# Sheet3.net
KiCad netlist of a schematic drawn in Altium Designer
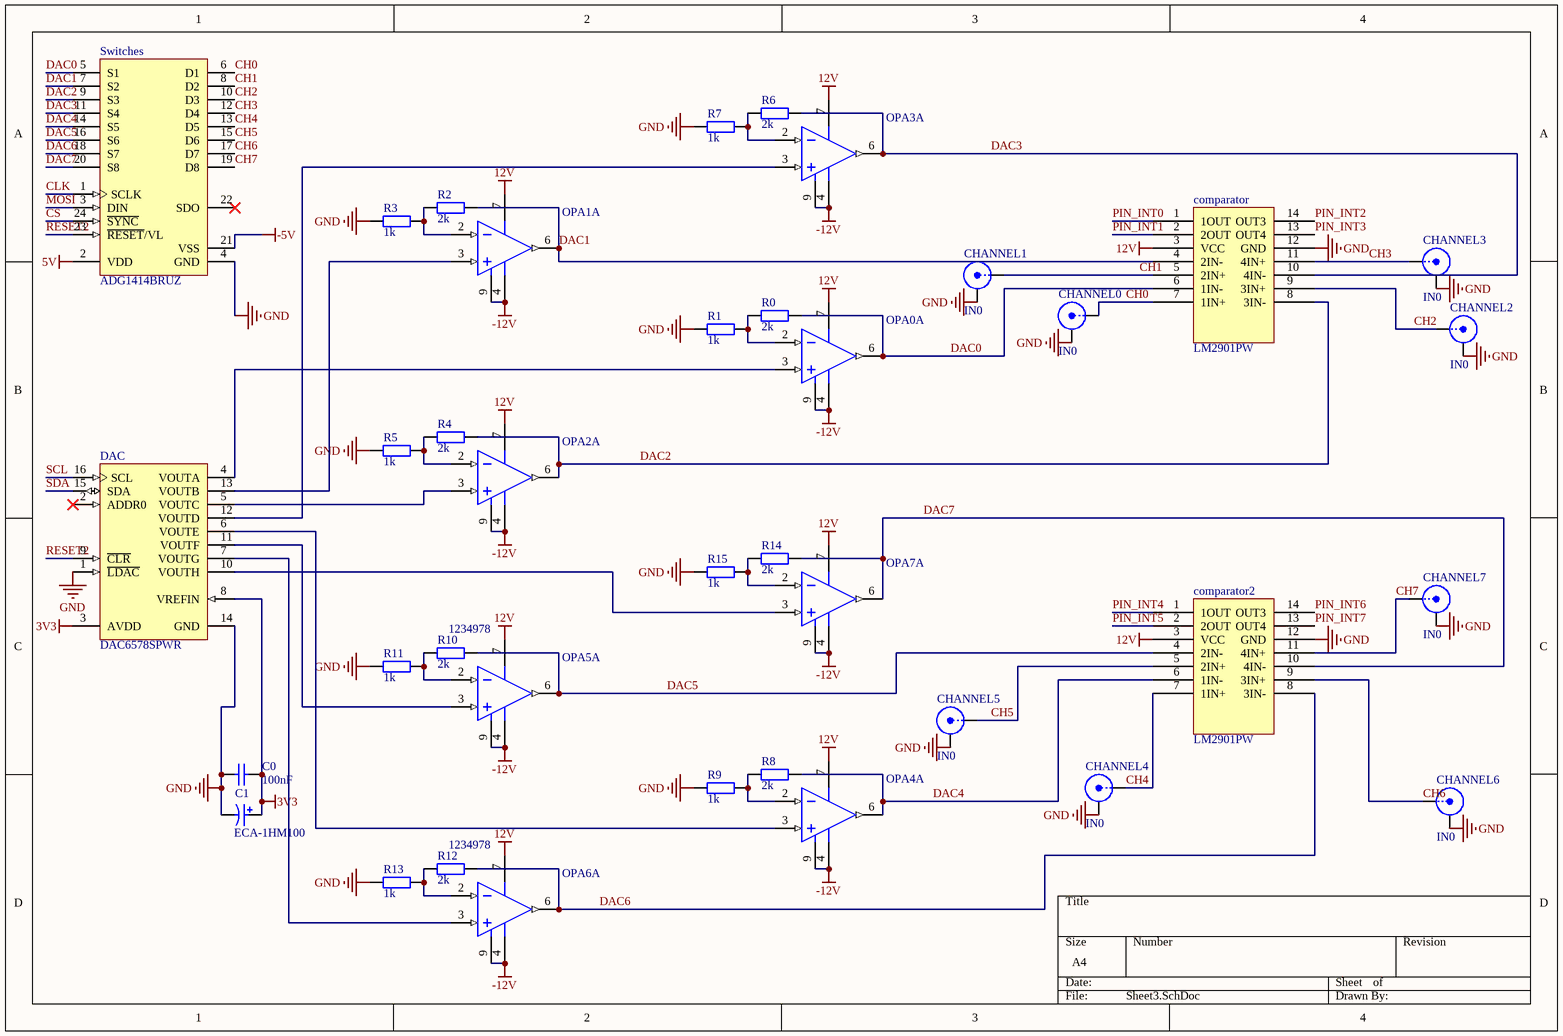
[diagram p0: Sheet3.SchDoc]

(export (version "E")
  (design (tool "Eeschema 10.0.6"))
  (components
    (comp (ref "C0")
      (value "100nF")
      (footprint "C0805")
      (description "Capacitor Cer 50V 0805 Vishay X7R")
      (libsource (lib "capacitors") (part "Ceramic 100nF/50V"))
    )
    (comp (ref "C1")
      (value "ECA-1HM100")
      (footprint "CAPPR55-200-1100X500X1200")
      (description "Aluminum Electrolytic Capacitor, 10 uF, +/- 20%, 50 V, -40 to 85 degC, 2-Pin THD, RoHS, Bulk")
      (libsource (lib "Altium Content Vault") (part "CMP-1665-00038-1"))
    )
    (comp (ref "CHANNEL0")
      (value "IN0")
      (footprint "connectors:SMB")
      (description "SMB Straight Connector")
      (fields (field (name "PUBLISHER") "Altium Limited"))
      (libsource (lib "connectors") (part "SMB"))
    )
    (comp (ref "CHANNEL1")
      (value "IN0")
      (footprint "connectors:SMB")
      (description "SMB Straight Connector")
      (fields (field (name "PUBLISHER") "Altium Limited"))
      (libsource (lib "connectors") (part "SMB"))
    )
    (comp (ref "CHANNEL2")
      (value "IN0")
      (footprint "connectors:SMB")
      (description "SMB Straight Connector")
      (fields (field (name "PUBLISHER") "Altium Limited"))
      (libsource (lib "connectors") (part "SMB"))
    )
    (comp (ref "CHANNEL3")
      (value "IN0")
      (footprint "connectors:SMB")
      (description "SMB Straight Connector")
      (fields (field (name "PUBLISHER") "Altium Limited"))
      (libsource (lib "connectors") (part "SMB"))
    )
    (comp (ref "CHANNEL4")
      (value "IN0")
      (footprint "connectors:SMB")
      (description "SMB Straight Connector")
      (fields (field (name "PUBLISHER") "Altium Limited"))
      (libsource (lib "connectors") (part "SMB"))
    )
    (comp (ref "CHANNEL5")
      (value "IN0")
      (footprint "connectors:SMB")
      (description "SMB Straight Connector")
      (fields (field (name "PUBLISHER") "Altium Limited"))
      (libsource (lib "connectors") (part "SMB"))
    )
    (comp (ref "CHANNEL6")
      (value "IN0")
      (footprint "connectors:SMB")
      (description "SMB Straight Connector")
      (fields (field (name "PUBLISHER") "Altium Limited"))
      (libsource (lib "connectors") (part "SMB"))
    )
    (comp (ref "CHANNEL7")
      (value "IN0")
      (footprint "connectors:SMB")
      (description "SMB Straight Connector")
      (fields (field (name "PUBLISHER") "Altium Limited"))
      (libsource (lib "connectors") (part "SMB"))
    )
    (comp (ref "comparator")
      (value "LM2901PW")
      (footprint "TSSOP-14")
      (libsource (lib "schlib") (part "LM2901PW"))
    )
    (comp (ref "comparator2")
      (value "LM2901PW")
      (footprint "TSSOP-14")
      (libsource (lib "schlib") (part "LM2901PW"))
    )
    (comp (ref "DAC")
      (value "DAC6578SPWR")
      (footprint "TI-PW16_N")
      (fields (field (name "MANUFACTURER") "Texas Instruments"))
      (libsource (lib "Altium Content Vault") (part "CMP-0004-01130-1"))
    )
    (comp (ref "OPA0")
      (value "THS3001IDGNG4")
      (footprint "TI-DGN8-1760X1425TP_N")
      (fields (field (name "MANUFACTURER") "Texas Instruments"))
      (libsource (lib "Altium Content Vault") (part "CMP-0016-00120-1"))
    )
    (comp (ref "OPA1")
      (value "THS3001IDGNG4")
      (footprint "TI-DGN8-1760X1425TP_N")
      (fields (field (name "MANUFACTURER") "Texas Instruments"))
      (libsource (lib "Altium Content Vault") (part "CMP-0016-00120-1"))
    )
    (comp (ref "OPA2")
      (value "THS3001IDGNG4")
      (footprint "TI-DGN8-1760X1425TP_N")
      (fields (field (name "MANUFACTURER") "Texas Instruments"))
      (libsource (lib "Altium Content Vault") (part "CMP-0016-00120-1"))
    )
    (comp (ref "OPA3")
      (value "THS3001IDGNG4")
      (footprint "TI-DGN8-1760X1425TP_N")
      (fields (field (name "MANUFACTURER") "Texas Instruments"))
      (libsource (lib "Altium Content Vault") (part "CMP-0016-00120-1"))
    )
    (comp (ref "OPA4")
      (value "THS3001IDGNG4")
      (footprint "TI-DGN8-1760X1425TP_N")
      (fields (field (name "MANUFACTURER") "Texas Instruments"))
      (libsource (lib "Altium Content Vault") (part "CMP-0016-00120-1"))
    )
    (comp (ref "OPA5")
      (value "THS3001IDGNG4")
      (footprint "TI-DGN8-1760X1425TP_N")
      (fields
        (field (name "MANUFACTURER") "Texas Instruments")
        (field (name "SUPPLIER PART NUMBER 1") "1234978")
      )
      (libsource (lib "Altium Content Vault") (part "CMP-0016-00120-1"))
    )
    (comp (ref "OPA6")
      (value "THS3001IDGNG4")
      (footprint "TI-DGN8-1760X1425TP_N")
      (fields
        (field (name "MANUFACTURER") "Texas Instruments")
        (field (name "SUPPLIER PART NUMBER 1") "1234978")
      )
      (libsource (lib "Altium Content Vault") (part "CMP-0016-00120-1"))
    )
    (comp (ref "OPA7")
      (value "THS3001IDGNG4")
      (footprint "TI-DGN8-1760X1425TP_N")
      (fields (field (name "MANUFACTURER") "Texas Instruments"))
      (libsource (lib "Altium Content Vault") (part "CMP-0016-00120-1"))
    )
    (comp (ref "R0")
      (value "2k")
      (footprint "6-0805_N")
      (description "Resistor")
      (fields (field (name "Comment") "1k-0W25-0805") (field (name "PUBLISHER") "Altium Limited"))
      (libsource (lib "resistors_0805") (part "1k-0W25-0805"))
    )
    (comp (ref "R1")
      (value "1k")
      (footprint "6-0805_N")
      (description "Resistor")
      (fields (field (name "Comment") "1k-0W25-0805") (field (name "PUBLISHER") "Altium Limited"))
      (libsource (lib "resistors_0805") (part "1k-0W25-0805"))
    )
    (comp (ref "R2")
      (value "2k")
      (footprint "6-0805_N")
      (description "Resistor")
      (fields (field (name "Comment") "1k-0W25-0805") (field (name "PUBLISHER") "Altium Limited"))
      (libsource (lib "resistors_0805") (part "1k-0W25-0805"))
    )
    (comp (ref "R3")
      (value "1k")
      (footprint "6-0805_N")
      (description "Resistor")
      (fields (field (name "Comment") "1k-0W25-0805") (field (name "PUBLISHER") "Altium Limited"))
      (libsource (lib "resistors_0805") (part "1k-0W25-0805"))
    )
    (comp (ref "R4")
      (value "2k")
      (footprint "6-0805_N")
      (description "Resistor")
      (fields (field (name "Comment") "1k-0W25-0805") (field (name "PUBLISHER") "Altium Limited"))
      (libsource (lib "resistors_0805") (part "1k-0W25-0805"))
    )
    (comp (ref "R5")
      (value "1k")
      (footprint "6-0805_N")
      (description "Resistor")
      (fields (field (name "Comment") "1k-0W25-0805") (field (name "PUBLISHER") "Altium Limited"))
      (libsource (lib "resistors_0805") (part "1k-0W25-0805"))
    )
    (comp (ref "R6")
      (value "2k")
      (footprint "6-0805_N")
      (description "Resistor")
      (fields (field (name "Comment") "1k-0W25-0805") (field (name "PUBLISHER") "Altium Limited"))
      (libsource (lib "resistors_0805") (part "1k-0W25-0805"))
    )
    (comp (ref "R7")
      (value "1k")
      (footprint "6-0805_N")
      (description "Resistor")
      (fields (field (name "Comment") "1k-0W25-0805") (field (name "PUBLISHER") "Altium Limited"))
      (libsource (lib "resistors_0805") (part "1k-0W25-0805"))
    )
    (comp (ref "R8")
      (value "2k")
      (footprint "6-0805_N")
      (description "Resistor")
      (fields (field (name "Comment") "1k-0W25-0805") (field (name "PUBLISHER") "Altium Limited"))
      (libsource (lib "resistors_0805") (part "1k-0W25-0805"))
    )
    (comp (ref "R9")
      (value "1k")
      (footprint "6-0805_N")
      (description "Resistor")
      (fields (field (name "Comment") "1k-0W25-0805") (field (name "PUBLISHER") "Altium Limited"))
      (libsource (lib "resistors_0805") (part "1k-0W25-0805"))
    )
    (comp (ref "R10")
      (value "2k")
      (footprint "6-0805_N")
      (description "Resistor")
      (fields (field (name "Comment") "1k-0W25-0805") (field (name "PUBLISHER") "Altium Limited"))
      (libsource (lib "resistors_0805") (part "1k-0W25-0805"))
    )
    (comp (ref "R11")
      (value "1k")
      (footprint "6-0805_N")
      (description "Resistor")
      (fields (field (name "Comment") "1k-0W25-0805") (field (name "PUBLISHER") "Altium Limited"))
      (libsource (lib "resistors_0805") (part "1k-0W25-0805"))
    )
    (comp (ref "R12")
      (value "2k")
      (footprint "6-0805_N")
      (description "Resistor")
      (fields (field (name "Comment") "1k-0W25-0805") (field (name "PUBLISHER") "Altium Limited"))
      (libsource (lib "resistors_0805") (part "1k-0W25-0805"))
    )
    (comp (ref "R13")
      (value "1k")
      (footprint "6-0805_N")
      (description "Resistor")
      (fields (field (name "Comment") "1k-0W25-0805") (field (name "PUBLISHER") "Altium Limited"))
      (libsource (lib "resistors_0805") (part "1k-0W25-0805"))
    )
    (comp (ref "R14")
      (value "2k")
      (footprint "6-0805_N")
      (description "Resistor")
      (fields (field (name "Comment") "1k-0W25-0805") (field (name "PUBLISHER") "Altium Limited"))
      (libsource (lib "resistors_0805") (part "1k-0W25-0805"))
    )
    (comp (ref "R15")
      (value "1k")
      (footprint "6-0805_N")
      (description "Resistor")
      (fields (field (name "Comment") "1k-0W25-0805") (field (name "PUBLISHER") "Altium Limited"))
      (libsource (lib "resistors_0805") (part "1k-0W25-0805"))
    )
    (comp (ref "Switches")
      (value "ADG1414BRUZ")
      (footprint "ADI-RU-24_N")
      (fields (field (name "MANUFACTURER") "Analog Devices"))
      (libsource (lib "Altium Content Vault") (part "CMP-0790-00247-1"))
    )
  )
  (nets
    (net (code "1") (name "-5V") (class "Default")
      (node (ref "Switches") (pin "21") (pinfunction "VSS_21") (pintype "power_in"))
    )
    (net (code "2") (name "-12V") (class "Default")
      (node (ref "OPA0") (pin "4") (pinfunction "VCC-_4") (pintype "power_in"))
      (node (ref "OPA0") (pin "9") (pinfunction "EP_9") (pintype "power_in"))
      (node (ref "OPA1") (pin "4") (pinfunction "VCC-_4") (pintype "power_in"))
      (node (ref "OPA1") (pin "9") (pinfunction "EP_9") (pintype "power_in"))
      (node (ref "OPA2") (pin "4") (pinfunction "VCC-_4") (pintype "power_in"))
      (node (ref "OPA2") (pin "9") (pinfunction "EP_9") (pintype "power_in"))
      (node (ref "OPA3") (pin "4") (pinfunction "VCC-_4") (pintype "power_in"))
      (node (ref "OPA3") (pin "9") (pinfunction "EP_9") (pintype "power_in"))
      (node (ref "OPA4") (pin "4") (pinfunction "VCC-_4") (pintype "power_in"))
      (node (ref "OPA4") (pin "9") (pinfunction "EP_9") (pintype "power_in"))
      (node (ref "OPA5") (pin "4") (pinfunction "VCC-_4") (pintype "power_in"))
      (node (ref "OPA5") (pin "9") (pinfunction "EP_9") (pintype "power_in"))
      (node (ref "OPA6") (pin "4") (pinfunction "VCC-_4") (pintype "power_in"))
      (node (ref "OPA6") (pin "9") (pinfunction "EP_9") (pintype "power_in"))
      (node (ref "OPA7") (pin "4") (pinfunction "VCC-_4") (pintype "power_in"))
      (node (ref "OPA7") (pin "9") (pinfunction "EP_9") (pintype "power_in"))
    )
    (net (code "3") (name "/CH0") (class "Default")
      (node (ref "CHANNEL0") (pin "1") (pinfunction "X_1") (pintype "passive"))
      (node (ref "Switches") (pin "6") (pinfunction "D1_6") (pintype "passive"))
      (node (ref "comparator") (pin "7") (pinfunction "1IN+_7") (pintype "passive"))
    )
    (net (code "4") (name "/CH1") (class "Default")
      (node (ref "CHANNEL1") (pin "1") (pinfunction "X_1") (pintype "passive"))
      (node (ref "Switches") (pin "8") (pinfunction "D2_8") (pintype "passive"))
      (node (ref "comparator") (pin "5") (pinfunction "2IN+_5") (pintype "passive"))
    )
    (net (code "5") (name "/CH2") (class "Default")
      (node (ref "CHANNEL2") (pin "1") (pinfunction "X_1") (pintype "passive"))
      (node (ref "Switches") (pin "10") (pinfunction "D3_10") (pintype "passive"))
      (node (ref "comparator") (pin "9") (pinfunction "3IN+_9") (pintype "passive"))
    )
    (net (code "6") (name "/CH3") (class "Default")
      (node (ref "CHANNEL3") (pin "1") (pinfunction "X_1") (pintype "passive"))
      (node (ref "Switches") (pin "12") (pinfunction "D4_12") (pintype "passive"))
      (node (ref "comparator") (pin "11") (pinfunction "4IN+_11") (pintype "passive"))
    )
    (net (code "7") (name "/CH4") (class "Default")
      (node (ref "CHANNEL4") (pin "1") (pinfunction "X_1") (pintype "passive"))
      (node (ref "Switches") (pin "13") (pinfunction "D5_13") (pintype "passive"))
      (node (ref "comparator2") (pin "7") (pinfunction "1IN+_7") (pintype "passive"))
    )
    (net (code "8") (name "/CH5") (class "Default")
      (node (ref "CHANNEL5") (pin "1") (pinfunction "X_1") (pintype "passive"))
      (node (ref "Switches") (pin "15") (pinfunction "D6_15") (pintype "passive"))
      (node (ref "comparator2") (pin "5") (pinfunction "2IN+_5") (pintype "passive"))
    )
    (net (code "9") (name "/CH6") (class "Default")
      (node (ref "CHANNEL6") (pin "1") (pinfunction "X_1") (pintype "passive"))
      (node (ref "Switches") (pin "17") (pinfunction "D7_17") (pintype "passive"))
      (node (ref "comparator2") (pin "9") (pinfunction "3IN+_9") (pintype "passive"))
    )
    (net (code "10") (name "/CH7") (class "Default")
      (node (ref "CHANNEL7") (pin "1") (pinfunction "X_1") (pintype "passive"))
      (node (ref "Switches") (pin "19") (pinfunction "D8_19") (pintype "passive"))
      (node (ref "comparator2") (pin "11") (pinfunction "4IN+_11") (pintype "passive"))
    )
    (net (code "11") (name "/CLK") (class "Default")
      (node (ref "Switches") (pin "1") (pinfunction "SCLK_1") (pintype "input"))
    )
    (net (code "12") (name "/CS") (class "Default")
      (node (ref "Switches") (pin "24") (pinfunction "~{SYNC}_24") (pintype "input"))
    )
    (net (code "13") (name "/DAC0") (class "Default")
      (node (ref "OPA0") (pin "6") (pinfunction "OUT_6") (pintype "output"))
      (node (ref "R0") (pin "2") (pinfunction "2_2") (pintype "passive"))
      (node (ref "Switches") (pin "5") (pinfunction "S1_5") (pintype "passive"))
      (node (ref "comparator") (pin "6") (pinfunction "1IN-_6") (pintype "passive"))
    )
    (net (code "14") (name "/DAC1") (class "Default")
      (node (ref "OPA1") (pin "6") (pinfunction "OUT_6") (pintype "output"))
      (node (ref "R2") (pin "2") (pinfunction "2_2") (pintype "passive"))
      (node (ref "Switches") (pin "7") (pinfunction "S2_7") (pintype "passive"))
      (node (ref "comparator") (pin "4") (pinfunction "2IN-_4") (pintype "passive"))
    )
    (net (code "15") (name "/DAC2") (class "Default")
      (node (ref "OPA2") (pin "6") (pinfunction "OUT_6") (pintype "output"))
      (node (ref "R4") (pin "2") (pinfunction "2_2") (pintype "passive"))
      (node (ref "Switches") (pin "9") (pinfunction "S3_9") (pintype "passive"))
      (node (ref "comparator") (pin "8") (pinfunction "3IN-_8") (pintype "passive"))
    )
    (net (code "16") (name "/DAC3") (class "Default")
      (node (ref "OPA3") (pin "6") (pinfunction "OUT_6") (pintype "output"))
      (node (ref "R6") (pin "2") (pinfunction "2_2") (pintype "passive"))
      (node (ref "Switches") (pin "11") (pinfunction "S4_11") (pintype "passive"))
      (node (ref "comparator") (pin "10") (pinfunction "4IN-_10") (pintype "passive"))
    )
    (net (code "17") (name "/DAC4") (class "Default")
      (node (ref "OPA4") (pin "6") (pinfunction "OUT_6") (pintype "output"))
      (node (ref "R8") (pin "2") (pinfunction "2_2") (pintype "passive"))
      (node (ref "Switches") (pin "14") (pinfunction "S5_14") (pintype "passive"))
      (node (ref "comparator2") (pin "6") (pinfunction "1IN-_6") (pintype "passive"))
    )
    (net (code "18") (name "/DAC5") (class "Default")
      (node (ref "OPA5") (pin "6") (pinfunction "OUT_6") (pintype "output"))
      (node (ref "R10") (pin "2") (pinfunction "2_2") (pintype "passive"))
      (node (ref "Switches") (pin "16") (pinfunction "S6_16") (pintype "passive"))
      (node (ref "comparator2") (pin "4") (pinfunction "2IN-_4") (pintype "passive"))
    )
    (net (code "19") (name "/DAC6") (class "Default")
      (node (ref "OPA6") (pin "6") (pinfunction "OUT_6") (pintype "output"))
      (node (ref "R12") (pin "2") (pinfunction "2_2") (pintype "passive"))
      (node (ref "Switches") (pin "18") (pinfunction "S7_18") (pintype "passive"))
      (node (ref "comparator2") (pin "8") (pinfunction "3IN-_8") (pintype "passive"))
    )
    (net (code "20") (name "/DAC7") (class "Default")
      (node (ref "OPA7") (pin "6") (pinfunction "OUT_6") (pintype "output"))
      (node (ref "R14") (pin "2") (pinfunction "2_2") (pintype "passive"))
      (node (ref "Switches") (pin "20") (pinfunction "S8_20") (pintype "passive"))
      (node (ref "comparator2") (pin "10") (pinfunction "4IN-_10") (pintype "passive"))
    )
    (net (code "21") (name "/MOSI") (class "Default")
      (node (ref "Switches") (pin "3") (pinfunction "DIN_3") (pintype "input"))
    )
    (net (code "22") (name "/PIN_INT0") (class "Default")
      (node (ref "comparator") (pin "1") (pinfunction "1OUT_1") (pintype "passive"))
    )
    (net (code "23") (name "/PIN_INT1") (class "Default")
      (node (ref "comparator") (pin "2") (pinfunction "2OUT_2") (pintype "passive"))
    )
    (net (code "24") (name "/PIN_INT2") (class "Default")
      (node (ref "comparator") (pin "14") (pinfunction "OUT3_14") (pintype "passive"))
    )
    (net (code "25") (name "/PIN_INT3") (class "Default")
      (node (ref "comparator") (pin "13") (pinfunction "OUT4_13") (pintype "passive"))
    )
    (net (code "26") (name "/PIN_INT4") (class "Default")
      (node (ref "comparator2") (pin "1") (pinfunction "1OUT_1") (pintype "passive"))
    )
    (net (code "27") (name "/PIN_INT5") (class "Default")
      (node (ref "comparator2") (pin "2") (pinfunction "2OUT_2") (pintype "passive"))
    )
    (net (code "28") (name "/PIN_INT6") (class "Default")
      (node (ref "comparator2") (pin "14") (pinfunction "OUT3_14") (pintype "passive"))
    )
    (net (code "29") (name "/PIN_INT7") (class "Default")
      (node (ref "comparator2") (pin "13") (pinfunction "OUT4_13") (pintype "passive"))
    )
    (net (code "30") (name "/RESET2") (class "Default")
      (node (ref "DAC") (pin "9") (pinfunction "~{CLR}_9") (pintype "input"))
      (node (ref "Switches") (pin "23") (pinfunction "~{RESET}/VL_23") (pintype "input"))
    )
    (net (code "31") (name "/SCL") (class "Default")
      (node (ref "DAC") (pin "16") (pinfunction "SCL_16") (pintype "input"))
    )
    (net (code "32") (name "/SDA") (class "Default")
      (node (ref "DAC") (pin "15") (pinfunction "SDA_15") (pintype "bidirectional"))
    )
    (net (code "33") (name "3V3") (class "Default")
      (node (ref "C0") (pin "2") (pinfunction "2_2") (pintype "passive"))
      (node (ref "C1") (pin "1") (pinfunction "1_1") (pintype "passive"))
      (node (ref "DAC") (pin "3") (pinfunction "AVDD_3") (pintype "power_in"))
      (node (ref "DAC") (pin "8") (pinfunction "VREFIN_8") (pintype "input"))
    )
    (net (code "34") (name "5V") (class "Default")
      (node (ref "Switches") (pin "2") (pinfunction "VDD_2") (pintype "power_in"))
    )
    (net (code "35") (name "12V") (class "Default")
      (node (ref "OPA0") (pin "7") (pinfunction "VCC+_7") (pintype "power_in"))
      (node (ref "OPA1") (pin "7") (pinfunction "VCC+_7") (pintype "power_in"))
      (node (ref "OPA2") (pin "7") (pinfunction "VCC+_7") (pintype "power_in"))
      (node (ref "OPA3") (pin "7") (pinfunction "VCC+_7") (pintype "power_in"))
      (node (ref "OPA4") (pin "7") (pinfunction "VCC+_7") (pintype "power_in"))
      (node (ref "OPA5") (pin "7") (pinfunction "VCC+_7") (pintype "power_in"))
      (node (ref "OPA6") (pin "7") (pinfunction "VCC+_7") (pintype "power_in"))
      (node (ref "OPA7") (pin "7") (pinfunction "VCC+_7") (pintype "power_in"))
      (node (ref "comparator") (pin "3") (pinfunction "VCC_3") (pintype "passive"))
      (node (ref "comparator2") (pin "3") (pinfunction "VCC_3") (pintype "passive"))
    )
    (net (code "36") (name "GND") (class "Default")
      (node (ref "C0") (pin "1") (pinfunction "1_1") (pintype "passive"))
      (node (ref "C1") (pin "2") (pinfunction "2_2") (pintype "passive"))
      (node (ref "CHANNEL0") (pin "2") (pinfunction "Y_2") (pintype "passive"))
      (node (ref "CHANNEL1") (pin "2") (pinfunction "Y_2") (pintype "passive"))
      (node (ref "CHANNEL2") (pin "2") (pinfunction "Y_2") (pintype "passive"))
      (node (ref "CHANNEL3") (pin "2") (pinfunction "Y_2") (pintype "passive"))
      (node (ref "CHANNEL4") (pin "2") (pinfunction "Y_2") (pintype "passive"))
      (node (ref "CHANNEL5") (pin "2") (pinfunction "Y_2") (pintype "passive"))
      (node (ref "CHANNEL6") (pin "2") (pinfunction "Y_2") (pintype "passive"))
      (node (ref "CHANNEL7") (pin "2") (pinfunction "Y_2") (pintype "passive"))
      (node (ref "DAC") (pin "1") (pinfunction "~{LDAC}_1") (pintype "input"))
      (node (ref "DAC") (pin "14") (pinfunction "GND_14") (pintype "power_in"))
      (node (ref "R1") (pin "1") (pinfunction "1_1") (pintype "passive"))
      (node (ref "R11") (pin "1") (pinfunction "1_1") (pintype "passive"))
      (node (ref "R13") (pin "1") (pinfunction "1_1") (pintype "passive"))
      (node (ref "R15") (pin "1") (pinfunction "1_1") (pintype "passive"))
      (node (ref "R3") (pin "1") (pinfunction "1_1") (pintype "passive"))
      (node (ref "R5") (pin "1") (pinfunction "1_1") (pintype "passive"))
      (node (ref "R7") (pin "1") (pinfunction "1_1") (pintype "passive"))
      (node (ref "R9") (pin "1") (pinfunction "1_1") (pintype "passive"))
      (node (ref "Switches") (pin "4") (pinfunction "GND_4") (pintype "power_in"))
      (node (ref "comparator") (pin "12") (pinfunction "GND_12") (pintype "passive"))
      (node (ref "comparator2") (pin "12") (pinfunction "GND_12") (pintype "passive"))
    )
    (net (code "37") (name "Net-(DAC-VOUTA)") (class "Default")
      (node (ref "DAC") (pin "4") (pinfunction "VOUTA_4") (pintype "tri_state"))
      (node (ref "OPA0") (pin "3") (pinfunction "IN+_3") (pintype "input"))
    )
    (net (code "38") (name "Net-(DAC-VOUTB)") (class "Default")
      (node (ref "DAC") (pin "13") (pinfunction "VOUTB_13") (pintype "tri_state"))
      (node (ref "OPA1") (pin "3") (pinfunction "IN+_3") (pintype "input"))
    )
    (net (code "39") (name "Net-(DAC-VOUTC)") (class "Default")
      (node (ref "DAC") (pin "5") (pinfunction "VOUTC_5") (pintype "tri_state"))
      (node (ref "OPA2") (pin "3") (pinfunction "IN+_3") (pintype "input"))
    )
    (net (code "40") (name "Net-(DAC-VOUTD)") (class "Default")
      (node (ref "DAC") (pin "12") (pinfunction "VOUTD_12") (pintype "tri_state"))
      (node (ref "OPA3") (pin "3") (pinfunction "IN+_3") (pintype "input"))
    )
    (net (code "41") (name "Net-(DAC-VOUTE)") (class "Default")
      (node (ref "DAC") (pin "6") (pinfunction "VOUTE_6") (pintype "tri_state"))
      (node (ref "OPA4") (pin "3") (pinfunction "IN+_3") (pintype "input"))
    )
    (net (code "42") (name "Net-(DAC-VOUTF)") (class "Default")
      (node (ref "DAC") (pin "11") (pinfunction "VOUTF_11") (pintype "tri_state"))
      (node (ref "OPA5") (pin "3") (pinfunction "IN+_3") (pintype "input"))
    )
    (net (code "43") (name "Net-(DAC-VOUTG)") (class "Default")
      (node (ref "DAC") (pin "7") (pinfunction "VOUTG_7") (pintype "tri_state"))
      (node (ref "OPA6") (pin "3") (pinfunction "IN+_3") (pintype "input"))
    )
    (net (code "44") (name "Net-(DAC-VOUTH)") (class "Default")
      (node (ref "DAC") (pin "10") (pinfunction "VOUTH_10") (pintype "tri_state"))
      (node (ref "OPA7") (pin "3") (pinfunction "IN+_3") (pintype "input"))
    )
    (net (code "45") (name "Net-(OPA0A-IN-)") (class "Default")
      (node (ref "OPA0") (pin "2") (pinfunction "IN-_2") (pintype "input"))
      (node (ref "R0") (pin "1") (pinfunction "1_1") (pintype "passive"))
      (node (ref "R1") (pin "2") (pinfunction "2_2") (pintype "passive"))
    )
    (net (code "46") (name "Net-(OPA1A-IN-)") (class "Default")
      (node (ref "OPA1") (pin "2") (pinfunction "IN-_2") (pintype "input"))
      (node (ref "R2") (pin "1") (pinfunction "1_1") (pintype "passive"))
      (node (ref "R3") (pin "2") (pinfunction "2_2") (pintype "passive"))
    )
    (net (code "47") (name "Net-(OPA2A-IN-)") (class "Default")
      (node (ref "OPA2") (pin "2") (pinfunction "IN-_2") (pintype "input"))
      (node (ref "R4") (pin "1") (pinfunction "1_1") (pintype "passive"))
      (node (ref "R5") (pin "2") (pinfunction "2_2") (pintype "passive"))
    )
    (net (code "48") (name "Net-(OPA3A-IN-)") (class "Default")
      (node (ref "OPA3") (pin "2") (pinfunction "IN-_2") (pintype "input"))
      (node (ref "R6") (pin "1") (pinfunction "1_1") (pintype "passive"))
      (node (ref "R7") (pin "2") (pinfunction "2_2") (pintype "passive"))
    )
    (net (code "49") (name "Net-(OPA4A-IN-)") (class "Default")
      (node (ref "OPA4") (pin "2") (pinfunction "IN-_2") (pintype "input"))
      (node (ref "R8") (pin "1") (pinfunction "1_1") (pintype "passive"))
      (node (ref "R9") (pin "2") (pinfunction "2_2") (pintype "passive"))
    )
    (net (code "50") (name "Net-(OPA5A-IN-)") (class "Default")
      (node (ref "OPA5") (pin "2") (pinfunction "IN-_2") (pintype "input"))
      (node (ref "R10") (pin "1") (pinfunction "1_1") (pintype "passive"))
      (node (ref "R11") (pin "2") (pinfunction "2_2") (pintype "passive"))
    )
    (net (code "51") (name "Net-(OPA6A-IN-)") (class "Default")
      (node (ref "OPA6") (pin "2") (pinfunction "IN-_2") (pintype "input"))
      (node (ref "R12") (pin "1") (pinfunction "1_1") (pintype "passive"))
      (node (ref "R13") (pin "2") (pinfunction "2_2") (pintype "passive"))
    )
    (net (code "52") (name "Net-(OPA7A-IN-)") (class "Default")
      (node (ref "OPA7") (pin "2") (pinfunction "IN-_2") (pintype "input"))
      (node (ref "R14") (pin "1") (pinfunction "1_1") (pintype "passive"))
      (node (ref "R15") (pin "2") (pinfunction "2_2") (pintype "passive"))
    )
    (net (code "53") (name "unconnected-(DAC-ADDR0-Pad2)") (class "Default")
      (node (ref "DAC") (pin "2") (pinfunction "ADDR0_2") (pintype "input+no_connect"))
    )
    (net (code "54") (name "unconnected-(Switches-SDO-Pad22)") (class "Default")
      (node (ref "Switches") (pin "22") (pinfunction "SDO_22") (pintype "open_collector+no_connect"))
    )
  )
)
